# Trless_Modular.net
KiCad netlist of a schematic drawn in EAGLE
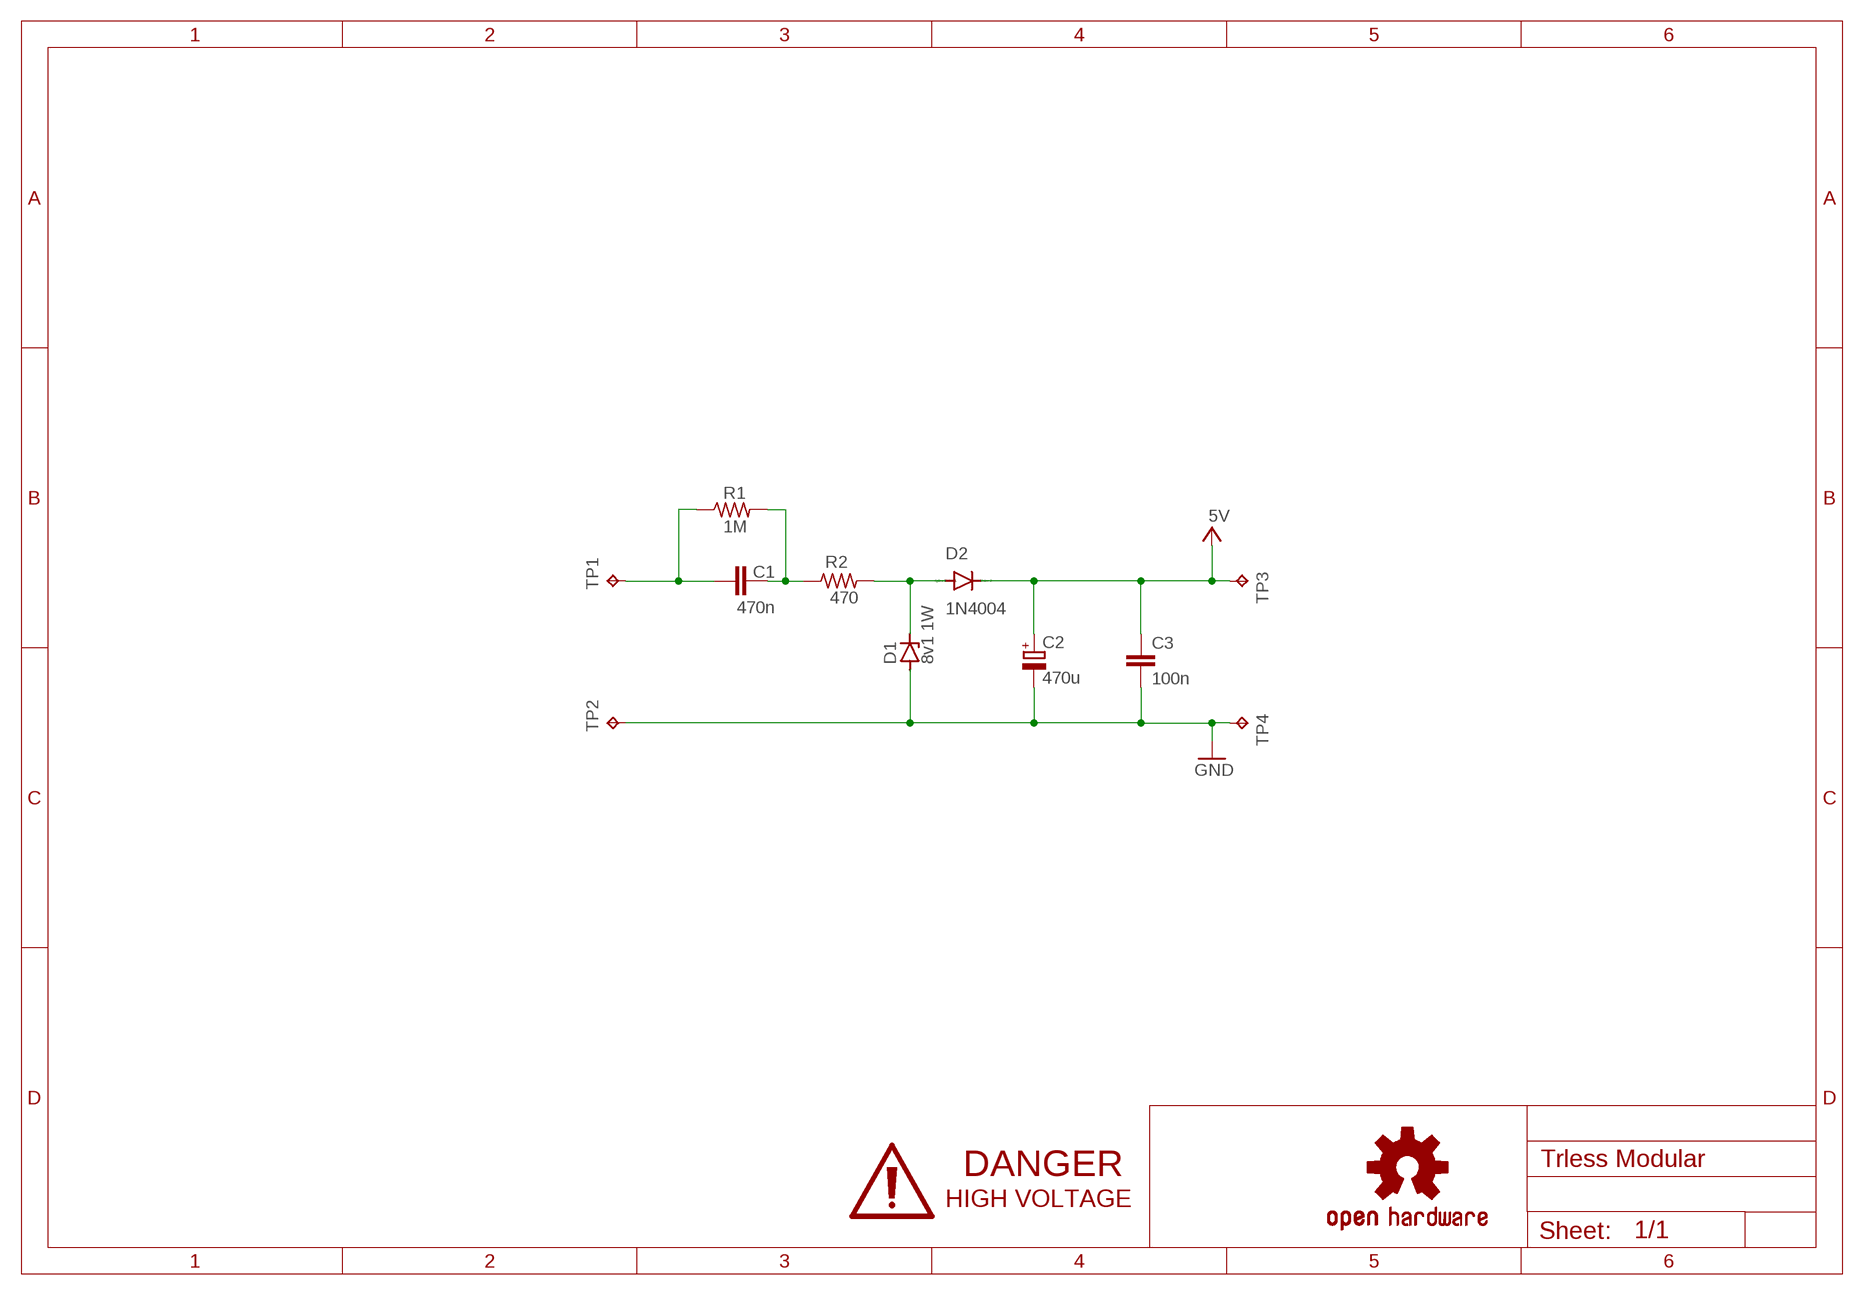
[diagram p0: schematic, sheet 1]

(export (version "E")
  (design (tool "Eeschema 10.0.6"))
  (components
    (comp (ref "C1")
      (value "470n")
      (footprint "eagle-import:C150-054X183")
      (libsource (lib "eagle-import") (part "C-EU150-054X183"))
    )
    (comp (ref "C2")
      (value "470u")
      (footprint "eagle-import:E3,5-8")
      (libsource (lib "eagle-import") (part "CPOL-EUE3.5-8"))
    )
    (comp (ref "C3")
      (value "100n")
      (footprint "eagle-import:C050-024X044")
      (libsource (lib "eagle-import") (part "C-EU050-024X044"))
    )
    (comp (ref "D1")
      (value "8v1 1W")
      (footprint "eagle-import:DO35Z10")
      (libsource (lib "eagle-import") (part "ZENER-DIODEDO35Z10"))
    )
    (comp (ref "D2")
      (value "1N4004")
      (footprint "eagle-import:DO41-10")
      (libsource (lib "eagle-import") (part "1N4004"))
    )
    (comp (ref "L2")
      (value "OSHW-LOGOS")
      (footprint "eagle-import:OSHW-LOGO-S")
      (libsource (lib "eagle-import") (part "OSHW-LOGOS"))
    )
    (comp (ref "R1")
      (value "1M")
      (footprint "eagle-import:0207_10")
      (libsource (lib "eagle-import") (part "R-US_0207/10"))
    )
    (comp (ref "R2")
      (value "470")
      (footprint "eagle-import:0207_10")
      (libsource (lib "eagle-import") (part "R-US_0207/10"))
    )
    (comp (ref "TP1")
      (value "TPPAD1-17")
      (footprint "eagle-import:P1-17")
      (libsource (lib "eagle-import") (part "TPPAD1-17"))
    )
    (comp (ref "TP2")
      (value "TPPAD1-17")
      (footprint "eagle-import:P1-17")
      (libsource (lib "eagle-import") (part "TPPAD1-17"))
    )
    (comp (ref "TP3")
      (value "TPPAD1-17")
      (footprint "eagle-import:P1-17")
      (libsource (lib "eagle-import") (part "TPPAD1-17"))
    )
    (comp (ref "TP4")
      (value "TPPAD1-17")
      (footprint "eagle-import:P1-17")
      (libsource (lib "eagle-import") (part "TPPAD1-17"))
    )
  )
  (nets
    (net (code "1") (name "5V") (class "Default")
      (node (ref "C2") (pin "+") (pinfunction "+_+") (pintype "passive"))
      (node (ref "C3") (pin "1") (pinfunction "1_1") (pintype "passive"))
      (node (ref "D2") (pin "C") (pinfunction "C_C") (pintype "passive"))
      (node (ref "TP3") (pin "TP") (pinfunction "TP_TP") (pintype "input"))
    )
    (net (code "2") (name "GND") (class "Default")
      (node (ref "C2") (pin "-") (pinfunction "-_-") (pintype "passive"))
      (node (ref "C3") (pin "2") (pinfunction "2_2") (pintype "passive"))
      (node (ref "D1") (pin "A") (pinfunction "A_A") (pintype "passive"))
      (node (ref "TP2") (pin "TP") (pinfunction "TP_TP") (pintype "input"))
      (node (ref "TP4") (pin "TP") (pinfunction "TP_TP") (pintype "input"))
    )
    (net (code "3") (name "Net-(C1-Pad1)") (class "Default")
      (node (ref "C1") (pin "1") (pinfunction "1_1") (pintype "passive"))
      (node (ref "R1") (pin "1") (pinfunction "1_1") (pintype "passive"))
      (node (ref "TP1") (pin "TP") (pinfunction "TP_TP") (pintype "input"))
    )
    (net (code "4") (name "Net-(C1-Pad2)") (class "Default")
      (node (ref "C1") (pin "2") (pinfunction "2_2") (pintype "passive"))
      (node (ref "R1") (pin "2") (pinfunction "2_2") (pintype "passive"))
      (node (ref "R2") (pin "1") (pinfunction "1_1") (pintype "passive"))
    )
    (net (code "5") (name "Net-(D1-PadC)") (class "Default")
      (node (ref "D1") (pin "C") (pinfunction "C_C") (pintype "passive"))
      (node (ref "D2") (pin "A") (pinfunction "A_A") (pintype "passive"))
      (node (ref "R2") (pin "2") (pinfunction "2_2") (pintype "passive"))
    )
  )
)
